# openSX70_ALADDIN_V38_20180122.net
KiCad netlist of a schematic drawn in EAGLE
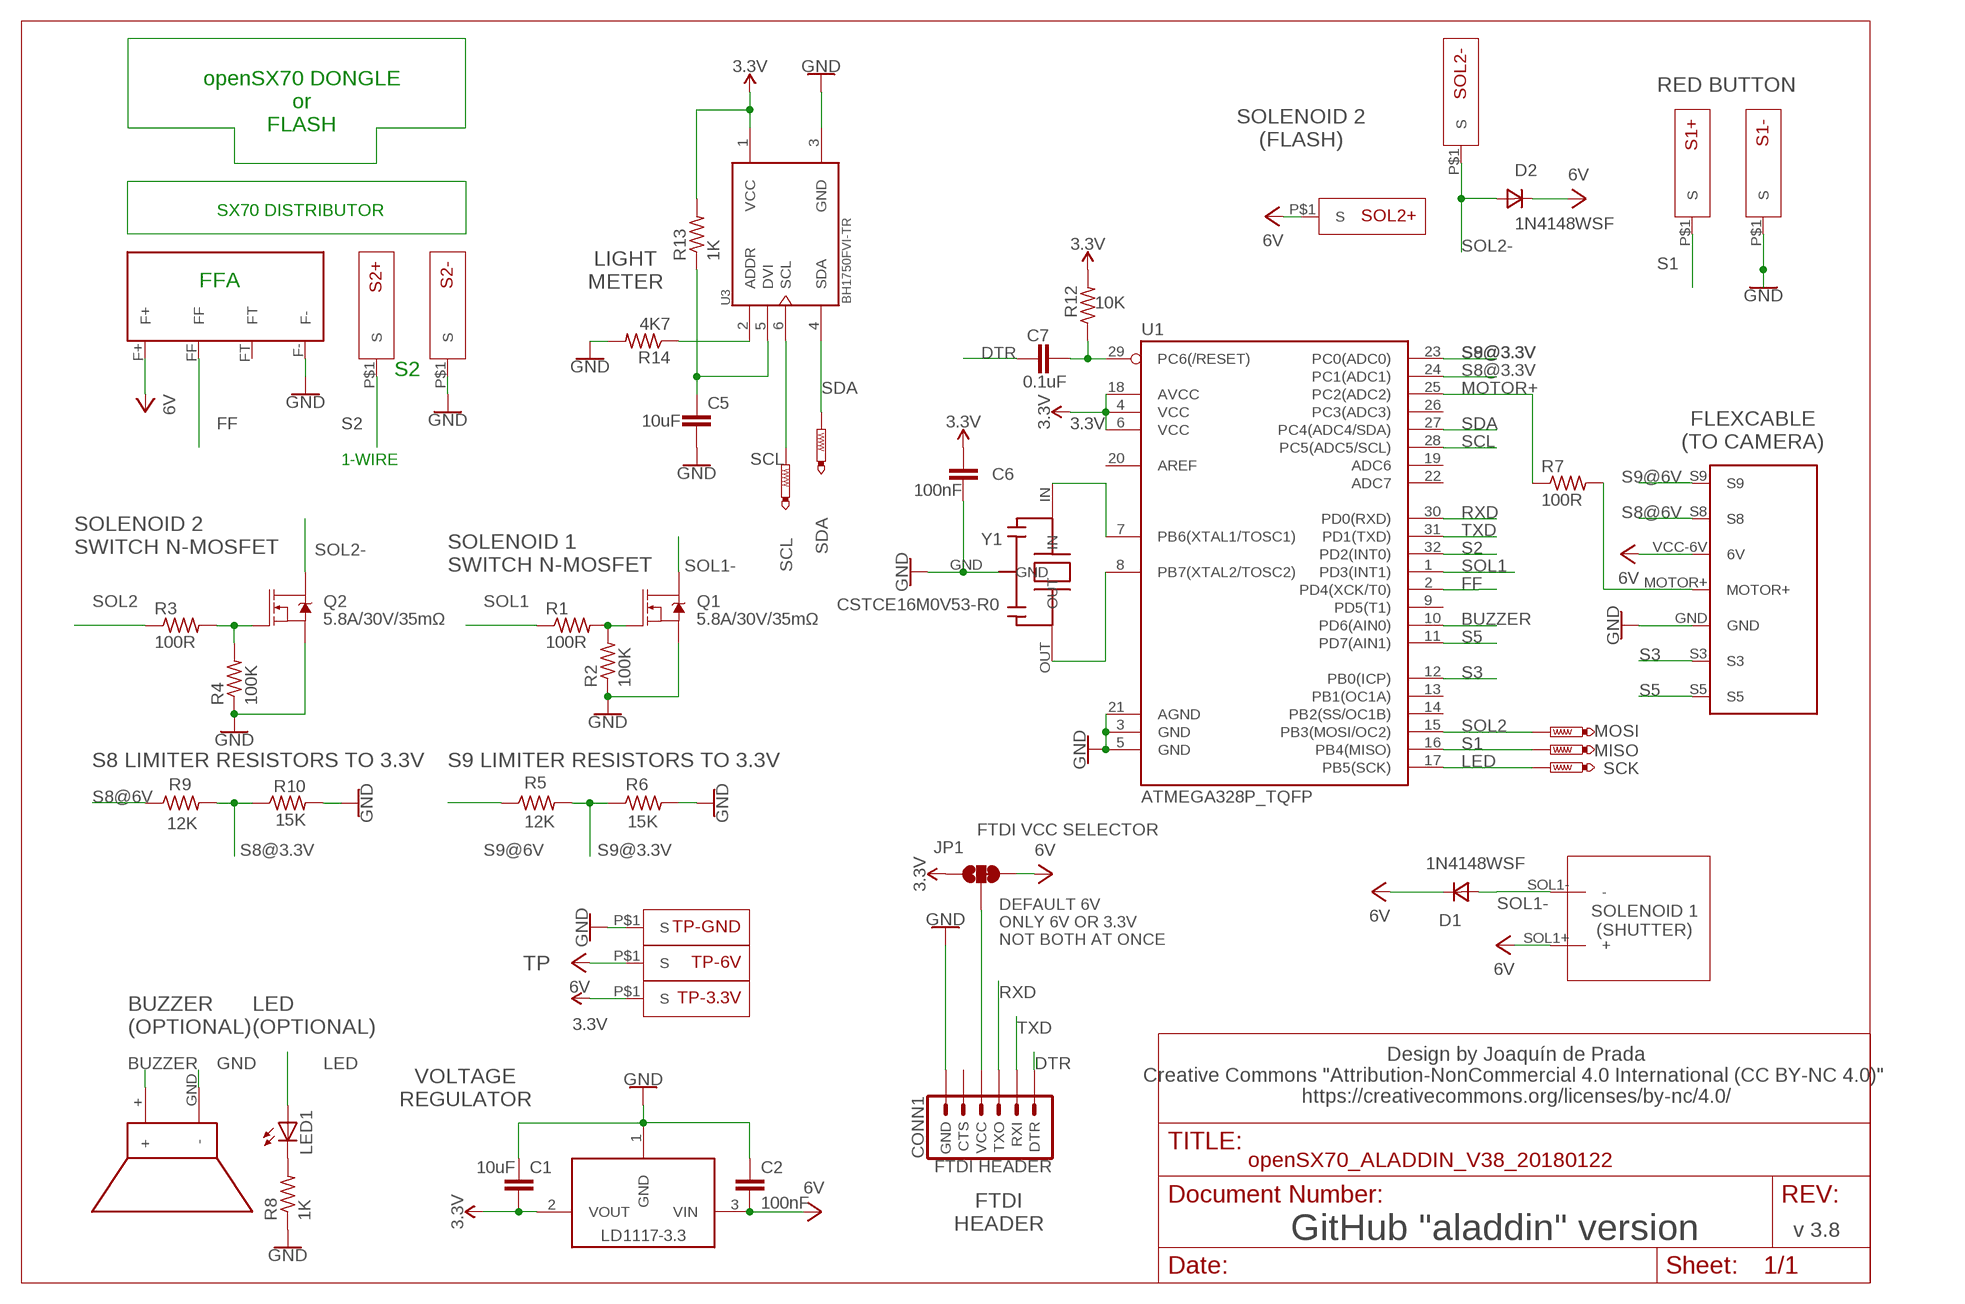
[diagram p0: schematic, sheet 1]

(export (version "E")
  (design (tool "Eeschema 10.0.6"))
  (components
    (comp (ref "BUZZ1")
      (value "CSET8-5G")
      (footprint "eagle-import:CSET8-5G_PACKAGE")
      (libsource (lib "eagle-import") (part "CSET8-5G"))
    )
    (comp (ref "C1")
      (value "10uF")
      (footprint "eagle-import:0603")
      (libsource (lib "eagle-import") (part "10UF-0603-6.3V-20%"))
    )
    (comp (ref "C2")
      (value "100nF")
      (footprint "eagle-import:C0603K")
      (libsource (lib "eagle-import") (part "C-EUC0603K"))
    )
    (comp (ref "C5")
      (value "10uF")
      (footprint "eagle-import:0603")
      (libsource (lib "eagle-import") (part "10UF-0603-6.3V-20%"))
    )
    (comp (ref "C6")
      (value "100nF")
      (footprint "eagle-import:C0603")
      (libsource (lib "eagle-import") (part "C-EUC0603"))
    )
    (comp (ref "C7")
      (value "0.1uF")
      (footprint "eagle-import:0603")
      (libsource (lib "eagle-import") (part "0.1UF-0603-25V-(+80/-20%)"))
    )
    (comp (ref "CONN1")
      (value "FTDI HEADER")
      (footprint "eagle-import:1X06")
      (libsource (lib "eagle-import") (part "6_PIN_SERIAL_TARGET"))
    )
    (comp (ref "D1")
      (value "1N4148WSF")
      (footprint "eagle-import:SOD323")
      (fields (field (name "MPN") "CDSOD323-T05C"))
      (libsource (lib "eagle-import") (part "DSOD323"))
    )
    (comp (ref "D2")
      (value "1N4148WSF")
      (footprint "eagle-import:SOD323")
      (fields (field (name "MPN") "CDSOD323-T05C"))
      (libsource (lib "eagle-import") (part "DSOD323"))
    )
    (comp (ref "JP1")
      (value "FTDI VCC SELECTOR")
      (footprint "eagle-import:SMT-JUMPER_3_1-NC_TRACE_SILK")
      (libsource (lib "eagle-import") (part "JUMPER-SMT_3_1-NC_TRACE_SILK"))
    )
    (comp (ref "LD11173.3V")
      (value "LD1117 3.3V")
      (footprint "eagle-import:SOT223")
      (fields (field (name "MF") "Advanced Monolithic Systems") (field (name "MP") "AMS1117-5.0"))
      (libsource (lib "eagle-import") (part "LD1117-3.3"))
    )
    (comp (ref "LED1")
      (value "LEDCHIPLED_0805")
      (footprint "eagle-import:CHIPLED_0805")
      (libsource (lib "eagle-import") (part "LEDCHIPLED_0805"))
    )
    (comp (ref "MISO")
      (value "PTR1TP08R")
      (footprint "eagle-import:TP08R")
      (libsource (lib "eagle-import") (part "PTR1TP08R"))
    )
    (comp (ref "MOSI")
      (value "PTR1TP08R")
      (footprint "eagle-import:TP08R")
      (libsource (lib "eagle-import") (part "PTR1TP08R"))
    )
    (comp (ref "Q1")
      (value "5.8A/30V/35mΩ")
      (footprint "eagle-import:SOT23-3")
      (libsource (lib "eagle-import") (part "MOSFET-NCH-AO3404A"))
    )
    (comp (ref "Q2")
      (value "5.8A/30V/35mΩ")
      (footprint "eagle-import:SOT23-3")
      (libsource (lib "eagle-import") (part "MOSFET-NCH-AO3404A"))
    )
    (comp (ref "R1")
      (value "100R")
      (footprint "eagle-import:R0603")
      (libsource (lib "eagle-import") (part "R-US_R0603"))
    )
    (comp (ref "R2")
      (value "100K")
      (footprint "eagle-import:R0603")
      (libsource (lib "eagle-import") (part "R-US_R0603"))
    )
    (comp (ref "R3")
      (value "100R")
      (footprint "eagle-import:R0603")
      (libsource (lib "eagle-import") (part "R-US_R0603"))
    )
    (comp (ref "R4")
      (value "100K")
      (footprint "eagle-import:R0603")
      (libsource (lib "eagle-import") (part "R-US_R0603"))
    )
    (comp (ref "R5")
      (value "12K")
      (footprint "eagle-import:R0603")
      (libsource (lib "eagle-import") (part "R-US_R0603"))
    )
    (comp (ref "R6")
      (value "15K")
      (footprint "eagle-import:R0603")
      (libsource (lib "eagle-import") (part "R-US_R0603"))
    )
    (comp (ref "R7")
      (value "100R")
      (footprint "eagle-import:R0603")
      (libsource (lib "eagle-import") (part "R-US_R0603"))
    )
    (comp (ref "R8")
      (value "1K")
      (footprint "eagle-import:R0603")
      (libsource (lib "eagle-import") (part "R-US_R0603"))
    )
    (comp (ref "R9")
      (value "12K")
      (footprint "eagle-import:R0603")
      (libsource (lib "eagle-import") (part "R-US_R0603"))
    )
    (comp (ref "R10")
      (value "15K")
      (footprint "eagle-import:R0603")
      (libsource (lib "eagle-import") (part "R-US_R0603"))
    )
    (comp (ref "R12")
      (value "10K")
      (footprint "eagle-import:R0603")
      (libsource (lib "eagle-import") (part "R-US_R0603"))
    )
    (comp (ref "R13")
      (value "1K")
      (footprint "eagle-import:R0603")
      (libsource (lib "eagle-import") (part "R-US_R0603"))
    )
    (comp (ref "R14")
      (value "4K7")
      (footprint "eagle-import:R0603")
      (libsource (lib "eagle-import") (part "R-US_R0603"))
    )
    (comp (ref "S1+")
      (value "SX70-S-PAD-NEW")
      (footprint "eagle-import:SX70-S-PAD2")
      (libsource (lib "eagle-import") (part "SX70-S-PAD-NEW"))
    )
    (comp (ref "S1-")
      (value "SX70-S-PAD-NEW")
      (footprint "eagle-import:SX70-S-PAD2")
      (libsource (lib "eagle-import") (part "SX70-S-PAD-NEW"))
    )
    (comp (ref "S2+")
      (value "SX70-S-PAD-NEW")
      (footprint "eagle-import:SX70-S-PAD2")
      (libsource (lib "eagle-import") (part "SX70-S-PAD-NEW"))
    )
    (comp (ref "S2-")
      (value "SX70-S-PAD-NEW")
      (footprint "eagle-import:SX70-S-PAD2")
      (libsource (lib "eagle-import") (part "SX70-S-PAD-NEW"))
    )
    (comp (ref "SCK")
      (value "PTR1TP08R")
      (footprint "eagle-import:TP08R")
      (libsource (lib "eagle-import") (part "PTR1TP08R"))
    )
    (comp (ref "SCL")
      (value "PTR1TP08R")
      (footprint "eagle-import:TP08R")
      (libsource (lib "eagle-import") (part "PTR1TP08R"))
    )
    (comp (ref "SDA")
      (value "PTR1TP08R")
      (footprint "eagle-import:TP08R")
      (libsource (lib "eagle-import") (part "PTR1TP08R"))
    )
    (comp (ref "SOL1")
      (value "SX70-SOLENOID1-2PADS")
      (footprint "eagle-import:SX70-SOLENOID1-2")
      (libsource (lib "eagle-import") (part "SX70-SOLENOID1-2PADS"))
    )
    (comp (ref "SOL2+")
      (value "SX70-S-PAD-NEW")
      (footprint "eagle-import:SX70-S-PAD2")
      (libsource (lib "eagle-import") (part "SX70-S-PAD-NEW"))
    )
    (comp (ref "SOL2-")
      (value "SX70-S-PAD-NEW")
      (footprint "eagle-import:SX70-S-PAD2")
      (libsource (lib "eagle-import") (part "SX70-S-PAD-NEW"))
    )
    (comp (ref "TP-3.3V")
      (value "SX70-S-PAD-NEW")
      (footprint "eagle-import:SX70-S-PAD2")
      (libsource (lib "eagle-import") (part "SX70-S-PAD-NEW"))
    )
    (comp (ref "TP-6V")
      (value "SX70-S-PAD-NEW")
      (footprint "eagle-import:SX70-S-PAD2")
      (libsource (lib "eagle-import") (part "SX70-S-PAD-NEW"))
    )
    (comp (ref "TP-GND")
      (value "SX70-S-PAD-NEW")
      (footprint "eagle-import:SX70-S-PAD2")
      (libsource (lib "eagle-import") (part "SX70-S-PAD-NEW"))
    )
    (comp (ref "U$1")
      (value "SX70-7-PAD")
      (footprint "eagle-import:SX70-7-PAD")
      (libsource (lib "eagle-import") (part "SX70-7-PAD"))
    )
    (comp (ref "U$2")
      (value "FFA")
      (footprint "eagle-import:FFA-PAD-PACKAGE")
      (libsource (lib "eagle-import") (part "SX70-FFA-PAD"))
    )
    (comp (ref "U1")
      (value "ATMEGA328P_TQFP")
      (footprint "eagle-import:TQFP32-08")
      (libsource (lib "eagle-import") (part "ATMEGA328P_TQFP"))
    )
    (comp (ref "U3")
      (value "BH1750FVI-TR")
      (footprint "eagle-import:SOTFL50P300X75-6N")
      (fields (field (name "MF") "Rohm"))
      (libsource (lib "eagle-import") (part "BH1750FVI-TR"))
    )
    (comp (ref "Y1")
      (value "CSTCE16M0V53-R0")
      (footprint "eagle-import:CFP95P160X100-3N")
      (fields (field (name "MF") "Murata"))
      (libsource (lib "eagle-import") (part "CSTCE16M0V53-R0"))
    )
  )
  (nets
    (net (code "1") (name "/BUZZER") (class "Default")
      (node (ref "BUZZ1") (pin "+") (pinfunction "+_+") (pintype "bidirectional"))
      (node (ref "U1") (pin "10") (pinfunction "PD6(AIN0)_10") (pintype "bidirectional"))
    )
    (net (code "2") (name "/DTR") (class "Default")
      (node (ref "C7") (pin "1") (pinfunction "1_1") (pintype "passive"))
      (node (ref "CONN1") (pin "1") (pinfunction "DTR_1") (pintype "passive"))
    )
    (net (code "3") (name "/FF") (class "Default")
      (node (ref "U$2") (pin "FF") (pinfunction "FF_FF") (pintype "bidirectional"))
      (node (ref "U1") (pin "2") (pinfunction "PD4(XCK/T0)_2") (pintype "bidirectional"))
    )
    (net (code "4") (name "/LED") (class "Default")
      (node (ref "LED1") (pin "A") (pinfunction "A_A") (pintype "passive"))
      (node (ref "SCK") (pin "TP") (pinfunction "TP_TP") (pintype "input"))
      (node (ref "U1") (pin "17") (pinfunction "PB5(SCK)_17") (pintype "bidirectional"))
    )
    (net (code "5") (name "/MOTOR+") (class "Default")
      (node (ref "R7") (pin "1") (pinfunction "1_1") (pintype "passive"))
      (node (ref "U1") (pin "25") (pinfunction "PC2(ADC2)_25") (pintype "bidirectional"))
    )
    (net (code "6") (name "/RXD") (class "Default")
      (node (ref "CONN1") (pin "3") (pinfunction "TXO_3") (pintype "passive"))
      (node (ref "U1") (pin "30") (pinfunction "PD0(RXD)_30") (pintype "bidirectional"))
    )
    (net (code "7") (name "/S1") (class "Default")
      (node (ref "MISO") (pin "TP") (pinfunction "TP_TP") (pintype "input"))
      (node (ref "S1+") (pin "P$1") (pinfunction "S_P$1") (pintype "bidirectional"))
      (node (ref "U1") (pin "16") (pinfunction "PB4(MISO)_16") (pintype "bidirectional"))
    )
    (net (code "8") (name "/S2") (class "Default")
      (node (ref "S2+") (pin "P$1") (pinfunction "S_P$1") (pintype "bidirectional"))
      (node (ref "U1") (pin "32") (pinfunction "PD2(INT0)_32") (pintype "bidirectional"))
    )
    (net (code "9") (name "/S3") (class "Default")
      (node (ref "U$1") (pin "S3") (pinfunction "S3_S3") (pintype "bidirectional"))
      (node (ref "U1") (pin "12") (pinfunction "PB0(ICP)_12") (pintype "bidirectional"))
    )
    (net (code "10") (name "/S5") (class "Default")
      (node (ref "U$1") (pin "S5") (pinfunction "S5_S5") (pintype "bidirectional"))
      (node (ref "U1") (pin "11") (pinfunction "PD7(AIN1)_11") (pintype "bidirectional"))
    )
    (net (code "11") (name "/S8@3.3V") (class "Default")
      (node (ref "R10") (pin "1") (pinfunction "1_1") (pintype "passive"))
      (node (ref "R9") (pin "2") (pinfunction "2_2") (pintype "passive"))
      (node (ref "U1") (pin "24") (pinfunction "PC1(ADC1)_24") (pintype "bidirectional"))
    )
    (net (code "12") (name "/S8@6V") (class "Default")
      (node (ref "R9") (pin "1") (pinfunction "1_1") (pintype "passive"))
      (node (ref "U$1") (pin "S8") (pinfunction "S8_S8") (pintype "bidirectional"))
    )
    (net (code "13") (name "/S9@3.3V") (class "Default")
      (node (ref "R5") (pin "2") (pinfunction "2_2") (pintype "passive"))
      (node (ref "R6") (pin "1") (pinfunction "1_1") (pintype "passive"))
      (node (ref "U1") (pin "23") (pinfunction "PC0(ADC0)_23") (pintype "bidirectional"))
    )
    (net (code "14") (name "/S9@6V") (class "Default")
      (node (ref "R5") (pin "1") (pinfunction "1_1") (pintype "passive"))
      (node (ref "U$1") (pin "S9") (pinfunction "S9_S9") (pintype "bidirectional"))
    )
    (net (code "15") (name "/SCL") (class "Default")
      (node (ref "SCL") (pin "TP") (pinfunction "TP_TP") (pintype "input"))
      (node (ref "U1") (pin "28") (pinfunction "PC5(ADC5/SCL)_28") (pintype "bidirectional"))
      (node (ref "U3") (pin "6") (pinfunction "SCL_6") (pintype "input"))
    )
    (net (code "16") (name "/SDA") (class "Default")
      (node (ref "SDA") (pin "TP") (pinfunction "TP_TP") (pintype "input"))
      (node (ref "U1") (pin "27") (pinfunction "PC4(ADC4/SDA)_27") (pintype "bidirectional"))
      (node (ref "U3") (pin "4") (pinfunction "SDA_4") (pintype "bidirectional"))
    )
    (net (code "17") (name "/SOL1") (class "Default")
      (node (ref "R1") (pin "1") (pinfunction "1_1") (pintype "passive"))
      (node (ref "U1") (pin "1") (pinfunction "PD3(INT1)_1") (pintype "bidirectional"))
    )
    (net (code "18") (name "/SOL1-") (class "Default")
      (node (ref "D1") (pin "2") (pinfunction "A_2") (pintype "passive"))
      (node (ref "Q1") (pin "3") (pinfunction "D_3") (pintype "bidirectional"))
      (node (ref "SOL1") (pin "SOL1-") (pinfunction "-_SOL1-") (pintype "bidirectional"))
    )
    (net (code "19") (name "/SOL2") (class "Default")
      (node (ref "MOSI") (pin "TP") (pinfunction "TP_TP") (pintype "input"))
      (node (ref "R3") (pin "1") (pinfunction "1_1") (pintype "passive"))
      (node (ref "U1") (pin "15") (pinfunction "PB3(MOSI/OC2)_15") (pintype "bidirectional"))
    )
    (net (code "20") (name "/SOL2-") (class "Default")
      (node (ref "D2") (pin "2") (pinfunction "A_2") (pintype "passive"))
      (node (ref "Q2") (pin "3") (pinfunction "D_3") (pintype "bidirectional"))
      (node (ref "SOL2-") (pin "P$1") (pinfunction "S_P$1") (pintype "bidirectional"))
    )
    (net (code "21") (name "/TXD") (class "Default")
      (node (ref "CONN1") (pin "2") (pinfunction "RXI_2") (pintype "passive"))
      (node (ref "U1") (pin "31") (pinfunction "PD1(TXD)_31") (pintype "bidirectional"))
    )
    (net (code "22") (name "3.3V") (class "Default")
      (node (ref "C1") (pin "2") (pinfunction "2_2") (pintype "passive"))
      (node (ref "C6") (pin "1") (pinfunction "1_1") (pintype "passive"))
      (node (ref "JP1") (pin "1") (pinfunction "1_1") (pintype "passive"))
      (node (ref "LD11173.3V") (pin "2") (pinfunction "VOUT_2") (pintype "bidirectional"))
      (node (ref "R12") (pin "2") (pinfunction "2_2") (pintype "passive"))
      (node (ref "R13") (pin "2") (pinfunction "2_2") (pintype "passive"))
      (node (ref "TP-3.3V") (pin "P$1") (pinfunction "S_P$1") (pintype "bidirectional"))
      (node (ref "U1") (pin "18") (pinfunction "AVCC_18") (pintype "bidirectional"))
      (node (ref "U1") (pin "4") (pinfunction "VCC_4") (pintype "bidirectional"))
      (node (ref "U1") (pin "6") (pinfunction "VCC_6") (pintype "bidirectional"))
      (node (ref "U3") (pin "1") (pinfunction "VCC_1") (pintype "power_in"))
    )
    (net (code "23") (name "6V") (class "Default")
      (node (ref "C2") (pin "2") (pinfunction "2_2") (pintype "passive"))
      (node (ref "D1") (pin "1") (pinfunction "C_1") (pintype "passive"))
      (node (ref "D2") (pin "1") (pinfunction "C_1") (pintype "passive"))
      (node (ref "JP1") (pin "3") (pinfunction "3_3") (pintype "passive"))
      (node (ref "LD11173.3V") (pin "3") (pinfunction "VIN_3") (pintype "bidirectional"))
      (node (ref "SOL1") (pin "SOL1+") (pinfunction "+_SOL1+") (pintype "bidirectional"))
      (node (ref "SOL2+") (pin "P$1") (pinfunction "S_P$1") (pintype "bidirectional"))
      (node (ref "TP-6V") (pin "P$1") (pinfunction "S_P$1") (pintype "bidirectional"))
      (node (ref "U$1") (pin "VCC-6V") (pinfunction "6V_VCC-6V") (pintype "bidirectional"))
      (node (ref "U$2") (pin "F+") (pinfunction "F+_F+") (pintype "bidirectional"))
    )
    (net (code "24") (name "GND") (class "Default")
      (node (ref "BUZZ1") (pin "GND") (pinfunction "-_GND") (pintype "bidirectional"))
      (node (ref "C1") (pin "1") (pinfunction "1_1") (pintype "passive"))
      (node (ref "C2") (pin "1") (pinfunction "1_1") (pintype "passive"))
      (node (ref "C5") (pin "2") (pinfunction "2_2") (pintype "passive"))
      (node (ref "C6") (pin "2") (pinfunction "2_2") (pintype "passive"))
      (node (ref "CONN1") (pin "6") (pinfunction "GND_6") (pintype "passive"))
      (node (ref "LD11173.3V") (pin "1") (pinfunction "GND_1") (pintype "bidirectional"))
      (node (ref "Q1") (pin "2") (pinfunction "S_2") (pintype "bidirectional"))
      (node (ref "Q2") (pin "2") (pinfunction "S_2") (pintype "bidirectional"))
      (node (ref "R10") (pin "2") (pinfunction "2_2") (pintype "passive"))
      (node (ref "R14") (pin "2") (pinfunction "2_2") (pintype "passive"))
      (node (ref "R2") (pin "1") (pinfunction "1_1") (pintype "passive"))
      (node (ref "R4") (pin "1") (pinfunction "1_1") (pintype "passive"))
      (node (ref "R6") (pin "2") (pinfunction "2_2") (pintype "passive"))
      (node (ref "R8") (pin "1") (pinfunction "1_1") (pintype "passive"))
      (node (ref "S1-") (pin "P$1") (pinfunction "S_P$1") (pintype "bidirectional"))
      (node (ref "S2-") (pin "P$1") (pinfunction "S_P$1") (pintype "bidirectional"))
      (node (ref "TP-GND") (pin "P$1") (pinfunction "S_P$1") (pintype "bidirectional"))
      (node (ref "U$1") (pin "GND") (pinfunction "GND_GND") (pintype "bidirectional"))
      (node (ref "U$2") (pin "F-") (pinfunction "F-_F-") (pintype "bidirectional"))
      (node (ref "U1") (pin "21") (pinfunction "AGND_21") (pintype "bidirectional"))
      (node (ref "U1") (pin "3") (pinfunction "GND_3") (pintype "bidirectional"))
      (node (ref "U1") (pin "5") (pinfunction "GND_5") (pintype "bidirectional"))
      (node (ref "U3") (pin "3") (pinfunction "GND_3") (pintype "power_in"))
      (node (ref "Y1") (pin "GND") (pinfunction "GND_GND") (pintype "passive"))
    )
    (net (code "25") (name "Net-(CONN1-VCC)") (class "Default")
      (node (ref "CONN1") (pin "4") (pinfunction "VCC_4") (pintype "passive"))
      (node (ref "JP1") (pin "2") (pinfunction "2_2") (pintype "passive"))
    )
    (net (code "26") (name "Net-(LED1-PadC)") (class "Default")
      (node (ref "LED1") (pin "C") (pinfunction "C_C") (pintype "passive"))
      (node (ref "R8") (pin "2") (pinfunction "2_2") (pintype "passive"))
    )
    (net (code "27") (name "Net-(Q1-G)") (class "Default")
      (node (ref "Q1") (pin "1") (pinfunction "G_1") (pintype "bidirectional"))
      (node (ref "R1") (pin "2") (pinfunction "2_2") (pintype "passive"))
      (node (ref "R2") (pin "2") (pinfunction "2_2") (pintype "passive"))
    )
    (net (code "28") (name "Net-(Q2-G)") (class "Default")
      (node (ref "Q2") (pin "1") (pinfunction "G_1") (pintype "bidirectional"))
      (node (ref "R3") (pin "2") (pinfunction "2_2") (pintype "passive"))
      (node (ref "R4") (pin "2") (pinfunction "2_2") (pintype "passive"))
    )
    (net (code "29") (name "Net-(R7-Pad2)") (class "Default")
      (node (ref "R7") (pin "2") (pinfunction "2_2") (pintype "passive"))
      (node (ref "U$1") (pin "MOTOR+") (pinfunction "MOTOR+_MOTOR+") (pintype "bidirectional"))
    )
    (net (code "30") (name "Net-(U1-PB6(XTAL1{slash}TOSC1))") (class "Default")
      (node (ref "U1") (pin "7") (pinfunction "PB6(XTAL1/TOSC1)_7") (pintype "bidirectional"))
      (node (ref "Y1") (pin "IN") (pinfunction "IN_IN") (pintype "input"))
    )
    (net (code "31") (name "Net-(U1-PB7(XTAL2{slash}TOSC2))") (class "Default")
      (node (ref "U1") (pin "8") (pinfunction "PB7(XTAL2/TOSC2)_8") (pintype "bidirectional"))
      (node (ref "Y1") (pin "OUT") (pinfunction "OUT_OUT") (pintype "output"))
    )
    (net (code "32") (name "Net-(U1-PC6({slash}RESET))") (class "Default")
      (node (ref "C7") (pin "2") (pinfunction "2_2") (pintype "passive"))
      (node (ref "R12") (pin "1") (pinfunction "1_1") (pintype "passive"))
      (node (ref "U1") (pin "29") (pinfunction "PC6(/RESET)_29") (pintype "bidirectional"))
    )
    (net (code "33") (name "Net-(U3-ADDR)") (class "Default")
      (node (ref "R14") (pin "1") (pinfunction "1_1") (pintype "passive"))
      (node (ref "U3") (pin "2") (pinfunction "ADDR_2") (pintype "input"))
    )
    (net (code "34") (name "Net-(U3-DVI)") (class "Default")
      (node (ref "C5") (pin "1") (pinfunction "1_1") (pintype "passive"))
      (node (ref "R13") (pin "1") (pinfunction "1_1") (pintype "passive"))
      (node (ref "U3") (pin "5") (pinfunction "DVI_5") (pintype "input"))
    )
    (net (code "35") (name "unconnected-(CONN1-CTS-Pad5)") (class "Default")
      (node (ref "CONN1") (pin "5") (pinfunction "CTS_5") (pintype "passive"))
    )
    (net (code "36") (name "unconnected-(U$2-PadFT)") (class "Default")
      (node (ref "U$2") (pin "FT") (pinfunction "FT_FT") (pintype "bidirectional"))
    )
    (net (code "37") (name "unconnected-(U1-ADC6-Pad19)") (class "Default")
      (node (ref "U1") (pin "19") (pinfunction "ADC6_19") (pintype "bidirectional"))
    )
    (net (code "38") (name "unconnected-(U1-ADC7-Pad22)") (class "Default")
      (node (ref "U1") (pin "22") (pinfunction "ADC7_22") (pintype "bidirectional"))
    )
    (net (code "39") (name "unconnected-(U1-AREF-Pad20)") (class "Default")
      (node (ref "U1") (pin "20") (pinfunction "AREF_20") (pintype "bidirectional"))
    )
    (net (code "40") (name "unconnected-(U1-PB1(OC1A)-Pad13)") (class "Default")
      (node (ref "U1") (pin "13") (pinfunction "PB1(OC1A)_13") (pintype "bidirectional"))
    )
    (net (code "41") (name "unconnected-(U1-PB2(SS{slash}OC1B)-Pad14)") (class "Default")
      (node (ref "U1") (pin "14") (pinfunction "PB2(SS/OC1B)_14") (pintype "bidirectional"))
    )
    (net (code "42") (name "unconnected-(U1-PC3(ADC3)-Pad26)") (class "Default")
      (node (ref "U1") (pin "26") (pinfunction "PC3(ADC3)_26") (pintype "bidirectional"))
    )
    (net (code "43") (name "unconnected-(U1-PD5(T1)-Pad9)") (class "Default")
      (node (ref "U1") (pin "9") (pinfunction "PD5(T1)_9") (pintype "bidirectional"))
    )
  )
)
